# untitled.net
KiCad netlist of a schematic drawn in EAGLE
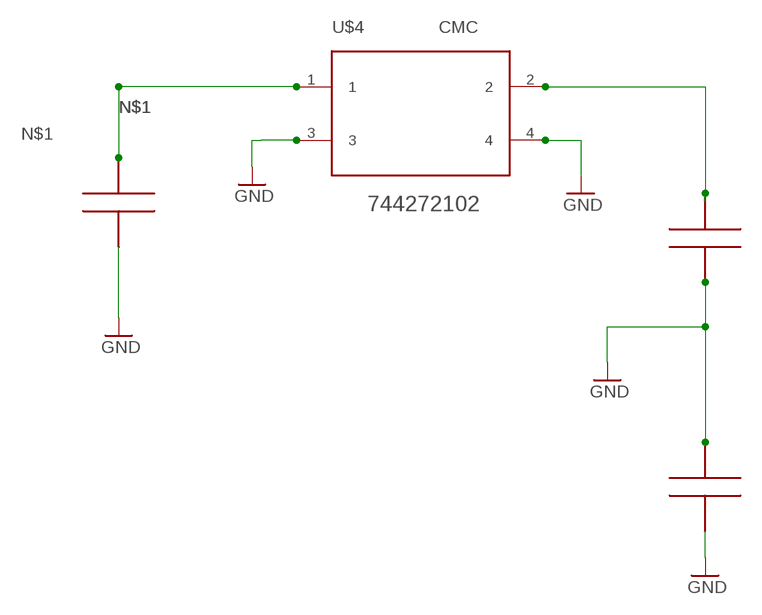
[diagram p0: schematic, sheet 1]

(export (version "E")
  (design (tool "Eeschema 10.0.6"))
  (components
    (comp (ref "C1")
      (value "CAPA1210")
      (footprint "eagle-import:FGJGFN")
      (libsource (lib "eagle-import") (part "CAPA1210"))
    )
    (comp (ref "C2")
      (value "CAPA1210")
      (footprint "eagle-import:FGJGFN")
      (libsource (lib "eagle-import") (part "CAPA1210"))
    )
    (comp (ref "U$3")
      (value "CAPA1210")
      (footprint "eagle-import:FGJGFN")
      (libsource (lib "eagle-import") (part "CAPA1210"))
    )
    (comp (ref "U$4")
      (value "CHOKE")
      (footprint "eagle-import:CHOKE")
      (libsource (lib "eagle-import") (part "CHOKE"))
    )
  )
  (nets
    (net (code "1") (name "/N$1") (class "Default")
      (node (ref "C1") (pin "2") (pinfunction "2_2") (pintype "passive"))
      (node (ref "U$4") (pin "1") (pinfunction "1_1") (pintype "passive"))
    )
    (net (code "2") (name "GND") (class "Default")
      (node (ref "C1") (pin "1") (pinfunction "1_1") (pintype "passive"))
      (node (ref "C2") (pin "1") (pinfunction "1_1") (pintype "passive"))
      (node (ref "U$3") (pin "1") (pinfunction "1_1") (pintype "passive"))
      (node (ref "U$3") (pin "2") (pinfunction "2_2") (pintype "passive"))
      (node (ref "U$4") (pin "3") (pinfunction "3_3") (pintype "passive"))
      (node (ref "U$4") (pin "4") (pinfunction "4_4") (pintype "passive"))
    )
    (net (code "3") (name "Net-(C2-Pad2)") (class "Default")
      (node (ref "C2") (pin "2") (pinfunction "2_2") (pintype "passive"))
      (node (ref "U$4") (pin "2") (pinfunction "2_2") (pintype "passive"))
    )
  )
)
